# MTX_pic_piggyback_BRW_qfn_V14.net
KiCad netlist of a schematic drawn in EAGLE
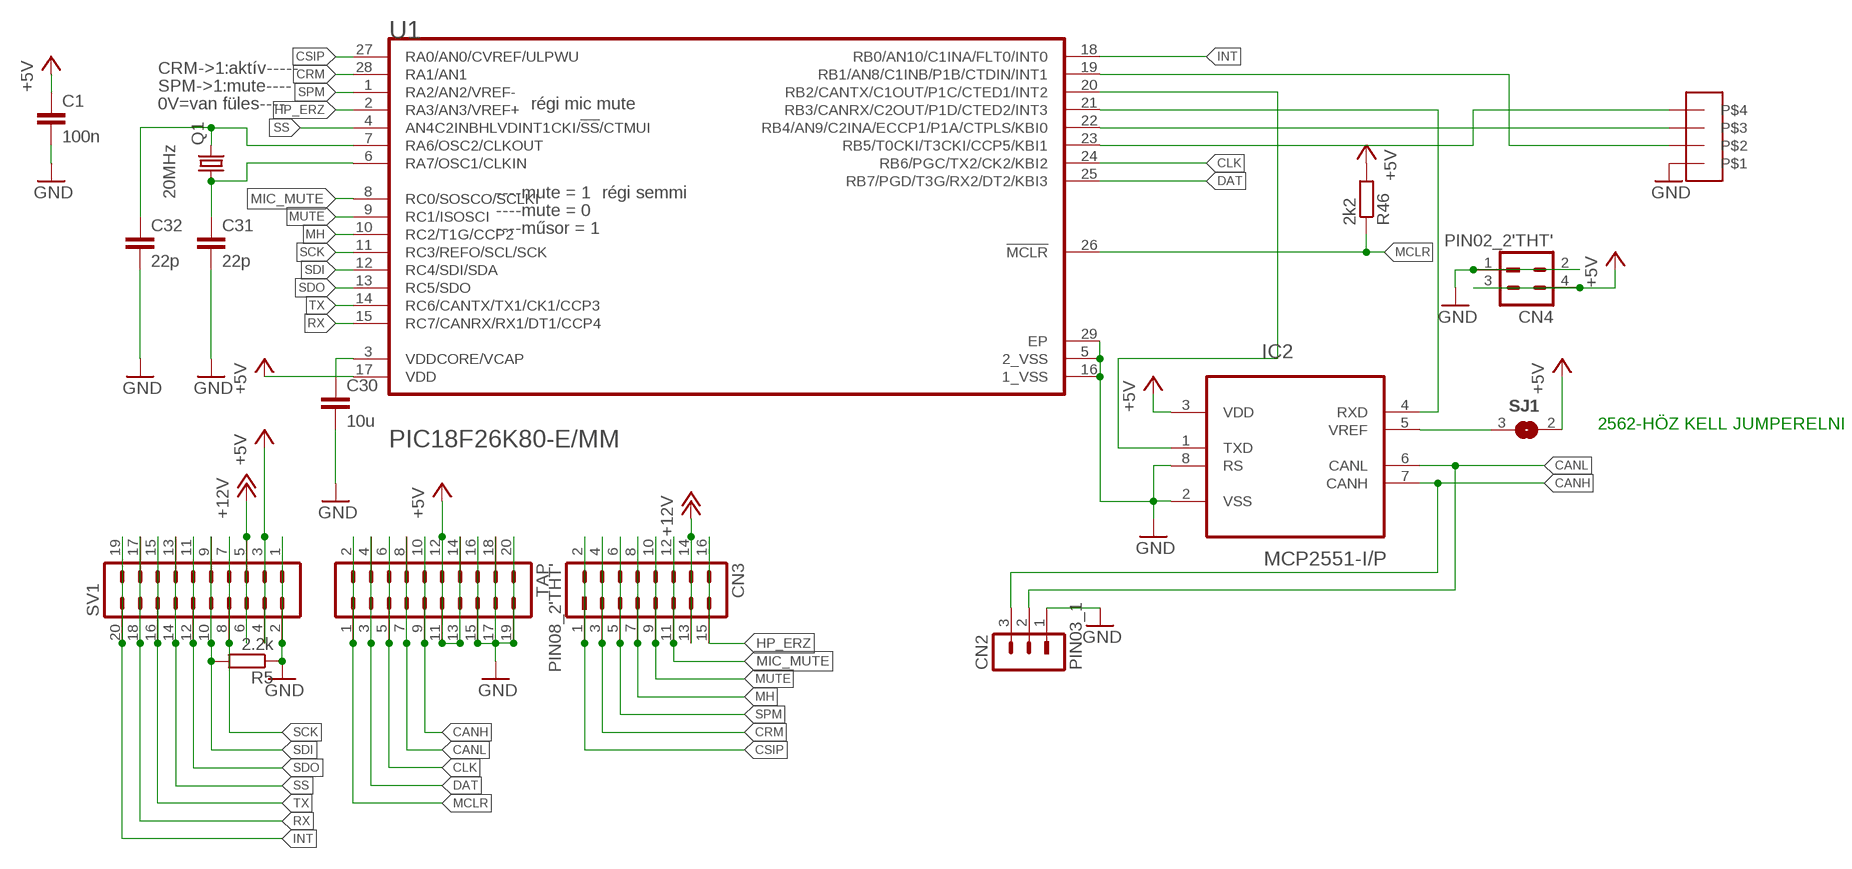
[diagram p0: schematic, sheet 1]

(export (version "E")
  (design (tool "Eeschema 10.0.6"))
  (components
    (comp (ref "C1")
      (value "100n")
      (footprint "eagle-import:C0805")
      (libsource (lib "eagle-import") (part "C-EUC0805"))
    )
    (comp (ref "C30")
      (value "10u")
      (footprint "eagle-import:C0805")
      (libsource (lib "eagle-import") (part "C-EUC0805"))
    )
    (comp (ref "C31")
      (value "22p")
      (footprint "eagle-import:C0805")
      (libsource (lib "eagle-import") (part "C-EUC0805"))
    )
    (comp (ref "C32")
      (value "22p")
      (footprint "eagle-import:C0805")
      (libsource (lib "eagle-import") (part "C-EUC0805"))
    )
    (comp (ref "CN2")
      (value "PIN03_1")
      (footprint "eagle-import:PIN03_1")
      (libsource (lib "eagle-import") (part "PIN03_1"))
    )
    (comp (ref "CN3")
      (value "PIN08_2'THT'")
      (footprint "eagle-import:PIN08_2")
      (libsource (lib "eagle-import") (part "PIN08_2'THT'"))
    )
    (comp (ref "CN4")
      (value "PIN02_2'THT'")
      (footprint "eagle-import:PIN02_2")
      (libsource (lib "eagle-import") (part "PIN02_2'THT'"))
    )
    (comp (ref "IC2")
      (value "MCP2551-I/P")
      (footprint "eagle-import:DIP254P762X432-8")
      (libsource (lib "eagle-import") (part "MCP2551-I/P"))
    )
    (comp (ref "Q1")
      (value "20MHz")
      (footprint "eagle-import:XTAL_QS")
      (libsource (lib "eagle-import") (part "XTAL_2QS"))
    )
    (comp (ref "R5")
      (value "2.2k")
      (footprint "eagle-import:R0805")
      (libsource (lib "eagle-import") (part "R-EU_R0805"))
    )
    (comp (ref "R46")
      (value "2k2")
      (footprint "eagle-import:R0805")
      (libsource (lib "eagle-import") (part "R-EU_R0805"))
    )
    (comp (ref "SJ1") (value "SJ") (footprint "eagle-import:SJ") (libsource (lib "eagle-import") (part "SJ")))
    (comp (ref "SV1")
      (value "MA10-2")
      (footprint "eagle-import:MA10-2")
      (libsource (lib "eagle-import") (part "MA10-2"))
    )
    (comp (ref "TAP")
      (value "MA10-2")
      (footprint "eagle-import:MA10-2")
      (libsource (lib "eagle-import") (part "MA10-2"))
    )
    (comp (ref "U$1")
      (value "FEHER_TUS_4")
      (footprint "eagle-import:FEHER_TUS_4")
      (libsource (lib "eagle-import") (part "FEHER_TUS_4"))
    )
    (comp (ref "U1")
      (value "MICROCHIP_PIC18F26K80-E-MMMICROCHIP_PIC18F26K80-E-MM_0_2")
      (footprint "eagle-import:MICROCHIP_PIC18F26K80-E-MM_2")
      (fields (field (name "MF") "Microchip") (field (name "MPN") "PIC18F26K80-E/MM"))
      (libsource (lib "eagle-import") (part "MICROCHIP_PIC18F26K80-E-MMMICROCHIP_PIC18F26K80-E-MM_0_2"))
    )
  )
  (nets
    (net (code "1") (name "+5V") (class "Default")
      (node (ref "C1") (pin "1") (pinfunction "1_1") (pintype "passive"))
      (node (ref "CN4") (pin "3") (pinfunction "3_3") (pintype "passive"))
      (node (ref "CN4") (pin "4") (pinfunction "4_4") (pintype "passive"))
      (node (ref "IC2") (pin "3") (pinfunction "VDD_3") (pintype "power_in"))
      (node (ref "R46") (pin "2") (pinfunction "2_2") (pintype "passive"))
      (node (ref "SJ1") (pin "2") (pinfunction "2_2") (pintype "passive"))
      (node (ref "SV1") (pin "3") (pinfunction "3_3") (pintype "passive"))
      (node (ref "SV1") (pin "4") (pinfunction "4_4") (pintype "passive"))
      (node (ref "TAP") (pin "11") (pinfunction "11_11") (pintype "passive"))
      (node (ref "TAP") (pin "12") (pinfunction "12_12") (pintype "passive"))
      (node (ref "TAP") (pin "13") (pinfunction "13_13") (pintype "passive"))
      (node (ref "TAP") (pin "14") (pinfunction "14_14") (pintype "passive"))
      (node (ref "U1") (pin "17") (pinfunction "VDD_17") (pintype "power_in"))
    )
    (net (code "2") (name "+12V") (class "Default")
      (node (ref "CN3") (pin "13") (pinfunction "13_13") (pintype "passive"))
      (node (ref "CN3") (pin "14") (pinfunction "14_14") (pintype "passive"))
      (node (ref "SV1") (pin "5") (pinfunction "5_5") (pintype "passive"))
      (node (ref "SV1") (pin "6") (pinfunction "6_6") (pintype "passive"))
    )
    (net (code "3") (name "CANH") (class "Default")
      (node (ref "CN2") (pin "3") (pinfunction "3_3") (pintype "passive"))
      (node (ref "IC2") (pin "7") (pinfunction "CANH_7") (pintype "bidirectional"))
      (node (ref "TAP") (pin "10") (pinfunction "10_10") (pintype "passive"))
      (node (ref "TAP") (pin "9") (pinfunction "9_9") (pintype "passive"))
    )
    (net (code "4") (name "CANL") (class "Default")
      (node (ref "CN2") (pin "2") (pinfunction "2_2") (pintype "passive"))
      (node (ref "IC2") (pin "6") (pinfunction "CANL_6") (pintype "bidirectional"))
      (node (ref "TAP") (pin "7") (pinfunction "7_7") (pintype "passive"))
      (node (ref "TAP") (pin "8") (pinfunction "8_8") (pintype "passive"))
    )
    (net (code "5") (name "CLK") (class "Default")
      (node (ref "TAP") (pin "5") (pinfunction "5_5") (pintype "passive"))
      (node (ref "TAP") (pin "6") (pinfunction "6_6") (pintype "passive"))
      (node (ref "U1") (pin "24") (pinfunction "RB6/PGC/TX2/CK2/KBI2_24") (pintype "bidirectional"))
    )
    (net (code "6") (name "CRM") (class "Default")
      (node (ref "CN3") (pin "3") (pinfunction "3_3") (pintype "passive"))
      (node (ref "CN3") (pin "4") (pinfunction "4_4") (pintype "passive"))
      (node (ref "U1") (pin "28") (pinfunction "RA1/AN1_28") (pintype "bidirectional"))
    )
    (net (code "7") (name "CSIP") (class "Default")
      (node (ref "CN3") (pin "1") (pinfunction "1_1") (pintype "passive"))
      (node (ref "CN3") (pin "2") (pinfunction "2_2") (pintype "passive"))
      (node (ref "U1") (pin "27") (pinfunction "RA0/AN0/CVREF/ULPWU_27") (pintype "bidirectional"))
    )
    (net (code "8") (name "DAT") (class "Default")
      (node (ref "TAP") (pin "3") (pinfunction "3_3") (pintype "passive"))
      (node (ref "TAP") (pin "4") (pinfunction "4_4") (pintype "passive"))
      (node (ref "U1") (pin "25") (pinfunction "RB7/PGD/T3G/RX2/DT2/KBI3_25") (pintype "bidirectional"))
    )
    (net (code "9") (name "GND") (class "Default")
      (node (ref "C1") (pin "2") (pinfunction "2_2") (pintype "passive"))
      (node (ref "C30") (pin "2") (pinfunction "2_2") (pintype "passive"))
      (node (ref "C31") (pin "2") (pinfunction "2_2") (pintype "passive"))
      (node (ref "C32") (pin "2") (pinfunction "2_2") (pintype "passive"))
      (node (ref "CN2") (pin "1") (pinfunction "1_1") (pintype "passive"))
      (node (ref "CN4") (pin "1") (pinfunction "1_1") (pintype "passive"))
      (node (ref "CN4") (pin "2") (pinfunction "2_2") (pintype "passive"))
      (node (ref "IC2") (pin "2") (pinfunction "VSS_2") (pintype "power_in"))
      (node (ref "IC2") (pin "8") (pinfunction "RS_8") (pintype "input"))
      (node (ref "R5") (pin "1") (pinfunction "1_1") (pintype "passive"))
      (node (ref "SV1") (pin "1") (pinfunction "1_1") (pintype "passive"))
      (node (ref "SV1") (pin "2") (pinfunction "2_2") (pintype "passive"))
      (node (ref "TAP") (pin "15") (pinfunction "15_15") (pintype "passive"))
      (node (ref "TAP") (pin "16") (pinfunction "16_16") (pintype "passive"))
      (node (ref "TAP") (pin "17") (pinfunction "17_17") (pintype "passive"))
      (node (ref "TAP") (pin "18") (pinfunction "18_18") (pintype "passive"))
      (node (ref "TAP") (pin "19") (pinfunction "19_19") (pintype "passive"))
      (node (ref "TAP") (pin "20") (pinfunction "20_20") (pintype "passive"))
      (node (ref "U$1") (pin "P$1") (pinfunction "P$1_P$1") (pintype "bidirectional"))
      (node (ref "U1") (pin "16") (pinfunction "1_VSS_16") (pintype "power_in"))
      (node (ref "U1") (pin "29") (pinfunction "EP_29") (pintype "power_in"))
      (node (ref "U1") (pin "5") (pinfunction "2_VSS_5") (pintype "power_in"))
    )
    (net (code "10") (name "HP_ERZ") (class "Default")
      (node (ref "CN3") (pin "15") (pinfunction "15_15") (pintype "passive"))
      (node (ref "CN3") (pin "16") (pinfunction "16_16") (pintype "passive"))
      (node (ref "U1") (pin "2") (pinfunction "RA3/AN3/VREF+_2") (pintype "bidirectional"))
    )
    (net (code "11") (name "INT") (class "Default")
      (node (ref "SV1") (pin "19") (pinfunction "19_19") (pintype "passive"))
      (node (ref "SV1") (pin "20") (pinfunction "20_20") (pintype "passive"))
      (node (ref "U1") (pin "18") (pinfunction "RB0/AN10/C1INA/FLT0/INT0_18") (pintype "bidirectional"))
    )
    (net (code "12") (name "MCLR") (class "Default")
      (node (ref "R46") (pin "1") (pinfunction "1_1") (pintype "passive"))
      (node (ref "TAP") (pin "1") (pinfunction "1_1") (pintype "passive"))
      (node (ref "TAP") (pin "2") (pinfunction "2_2") (pintype "passive"))
      (node (ref "U1") (pin "26") (pinfunction "~{MCLR}_26") (pintype "input"))
    )
    (net (code "13") (name "MH") (class "Default")
      (node (ref "CN3") (pin "7") (pinfunction "7_7") (pintype "passive"))
      (node (ref "CN3") (pin "8") (pinfunction "8_8") (pintype "passive"))
      (node (ref "U1") (pin "10") (pinfunction "RC2/T1G/CCP2_10") (pintype "bidirectional"))
    )
    (net (code "14") (name "MIC_MUTE") (class "Default")
      (node (ref "CN3") (pin "11") (pinfunction "11_11") (pintype "passive"))
      (node (ref "CN3") (pin "12") (pinfunction "12_12") (pintype "passive"))
      (node (ref "U1") (pin "8") (pinfunction "RC0/SOSCO/SCLKI_8") (pintype "bidirectional"))
    )
    (net (code "15") (name "MUTE") (class "Default")
      (node (ref "CN3") (pin "10") (pinfunction "10_10") (pintype "passive"))
      (node (ref "CN3") (pin "9") (pinfunction "9_9") (pintype "passive"))
      (node (ref "U1") (pin "9") (pinfunction "RC1/ISOSCI_9") (pintype "bidirectional"))
    )
    (net (code "16") (name "Net-(IC2-RXD)") (class "Default")
      (node (ref "IC2") (pin "4") (pinfunction "RXD_4") (pintype "output"))
      (node (ref "U1") (pin "21") (pinfunction "RB3/CANRX/C2OUT/P1D/CTED2/INT3_21") (pintype "bidirectional"))
    )
    (net (code "17") (name "Net-(IC2-TXD)") (class "Default")
      (node (ref "IC2") (pin "1") (pinfunction "TXD_1") (pintype "input"))
      (node (ref "U1") (pin "20") (pinfunction "RB2/CANTX/C1OUT/P1C/CTED1/INT2_20") (pintype "bidirectional"))
    )
    (net (code "18") (name "Net-(IC2-VREF)") (class "Default")
      (node (ref "IC2") (pin "5") (pinfunction "VREF_5") (pintype "output"))
      (node (ref "SJ1") (pin "3") (pinfunction "1_3") (pintype "passive"))
    )
    (net (code "19") (name "Net-(U1-RA6{slash}OSC2{slash}CLKOUT)") (class "Default")
      (node (ref "C32") (pin "1") (pinfunction "1_1") (pintype "passive"))
      (node (ref "Q1") (pin "2") (pinfunction "2_2") (pintype "passive"))
      (node (ref "U1") (pin "7") (pinfunction "RA6/OSC2/CLKOUT_7") (pintype "bidirectional"))
    )
    (net (code "20") (name "Net-(U1-RA7{slash}OSC1{slash}CLKIN)") (class "Default")
      (node (ref "C31") (pin "1") (pinfunction "1_1") (pintype "passive"))
      (node (ref "Q1") (pin "1") (pinfunction "1_1") (pintype "passive"))
      (node (ref "U1") (pin "6") (pinfunction "RA7/OSC1/CLKIN_6") (pintype "bidirectional"))
    )
    (net (code "21") (name "Net-(U1-RB1{slash}AN8{slash}C1INB{slash}P1B{slash}CTDIN{slash}INT1)") (class "Default")
      (node (ref "U$1") (pin "P$2") (pinfunction "P$2_P$2") (pintype "bidirectional"))
      (node (ref "U1") (pin "19") (pinfunction "RB1/AN8/C1INB/P1B/CTDIN/INT1_19") (pintype "bidirectional"))
    )
    (net (code "22") (name "Net-(U1-RB4{slash}AN9{slash}C2INA{slash}ECCP1{slash}P1A{slash}CTPLS{slash}KBI0)") (class "Default")
      (node (ref "U$1") (pin "P$3") (pinfunction "P$3_P$3") (pintype "bidirectional"))
      (node (ref "U1") (pin "22") (pinfunction "RB4/AN9/C2INA/ECCP1/P1A/CTPLS/KBI0_22") (pintype "bidirectional"))
    )
    (net (code "23") (name "Net-(U1-RB5{slash}T0CKI{slash}T3CKI{slash}CCP5{slash}KBI1)") (class "Default")
      (node (ref "U$1") (pin "P$4") (pinfunction "P$4_P$4") (pintype "bidirectional"))
      (node (ref "U1") (pin "23") (pinfunction "RB5/T0CKI/T3CKI/CCP5/KBI1_23") (pintype "bidirectional"))
    )
    (net (code "24") (name "Net-(U1-VDDCORE{slash}VCAP)") (class "Default")
      (node (ref "C30") (pin "1") (pinfunction "1_1") (pintype "passive"))
      (node (ref "U1") (pin "3") (pinfunction "VDDCORE/VCAP_3") (pintype "power_in"))
    )
    (net (code "25") (name "RX") (class "Default")
      (node (ref "SV1") (pin "17") (pinfunction "17_17") (pintype "passive"))
      (node (ref "SV1") (pin "18") (pinfunction "18_18") (pintype "passive"))
      (node (ref "U1") (pin "15") (pinfunction "RC7/CANRX/RX1/DT1/CCP4_15") (pintype "bidirectional"))
    )
    (net (code "26") (name "SCK") (class "Default")
      (node (ref "SV1") (pin "7") (pinfunction "7_7") (pintype "passive"))
      (node (ref "SV1") (pin "8") (pinfunction "8_8") (pintype "passive"))
      (node (ref "U1") (pin "11") (pinfunction "RC3/REFO/SCL/SCK_11") (pintype "bidirectional"))
    )
    (net (code "27") (name "SDI") (class "Default")
      (node (ref "R5") (pin "2") (pinfunction "2_2") (pintype "passive"))
      (node (ref "SV1") (pin "10") (pinfunction "10_10") (pintype "passive"))
      (node (ref "SV1") (pin "9") (pinfunction "9_9") (pintype "passive"))
      (node (ref "U1") (pin "12") (pinfunction "RC4/SDI/SDA_12") (pintype "bidirectional"))
    )
    (net (code "28") (name "SDO") (class "Default")
      (node (ref "SV1") (pin "11") (pinfunction "11_11") (pintype "passive"))
      (node (ref "SV1") (pin "12") (pinfunction "12_12") (pintype "passive"))
      (node (ref "U1") (pin "13") (pinfunction "RC5/SDO_13") (pintype "bidirectional"))
    )
    (net (code "29") (name "SPM") (class "Default")
      (node (ref "CN3") (pin "5") (pinfunction "5_5") (pintype "passive"))
      (node (ref "CN3") (pin "6") (pinfunction "6_6") (pintype "passive"))
      (node (ref "U1") (pin "1") (pinfunction "RA2/AN2/VREF-_1") (pintype "bidirectional"))
    )
    (net (code "30") (name "SS") (class "Default")
      (node (ref "SV1") (pin "13") (pinfunction "13_13") (pintype "passive"))
      (node (ref "SV1") (pin "14") (pinfunction "14_14") (pintype "passive"))
      (node (ref "U1") (pin "4") (pinfunction "AN4C2INBHLVDINT1CKI/~{SS}/CTMUI_4") (pintype "bidirectional"))
    )
    (net (code "31") (name "TX") (class "Default")
      (node (ref "SV1") (pin "15") (pinfunction "15_15") (pintype "passive"))
      (node (ref "SV1") (pin "16") (pinfunction "16_16") (pintype "passive"))
      (node (ref "U1") (pin "14") (pinfunction "RC6/CANTX/TX1/CK1/CCP3_14") (pintype "bidirectional"))
    )
  )
)
